# mcu.net
KiCad netlist of a schematic drawn in Altium Designer
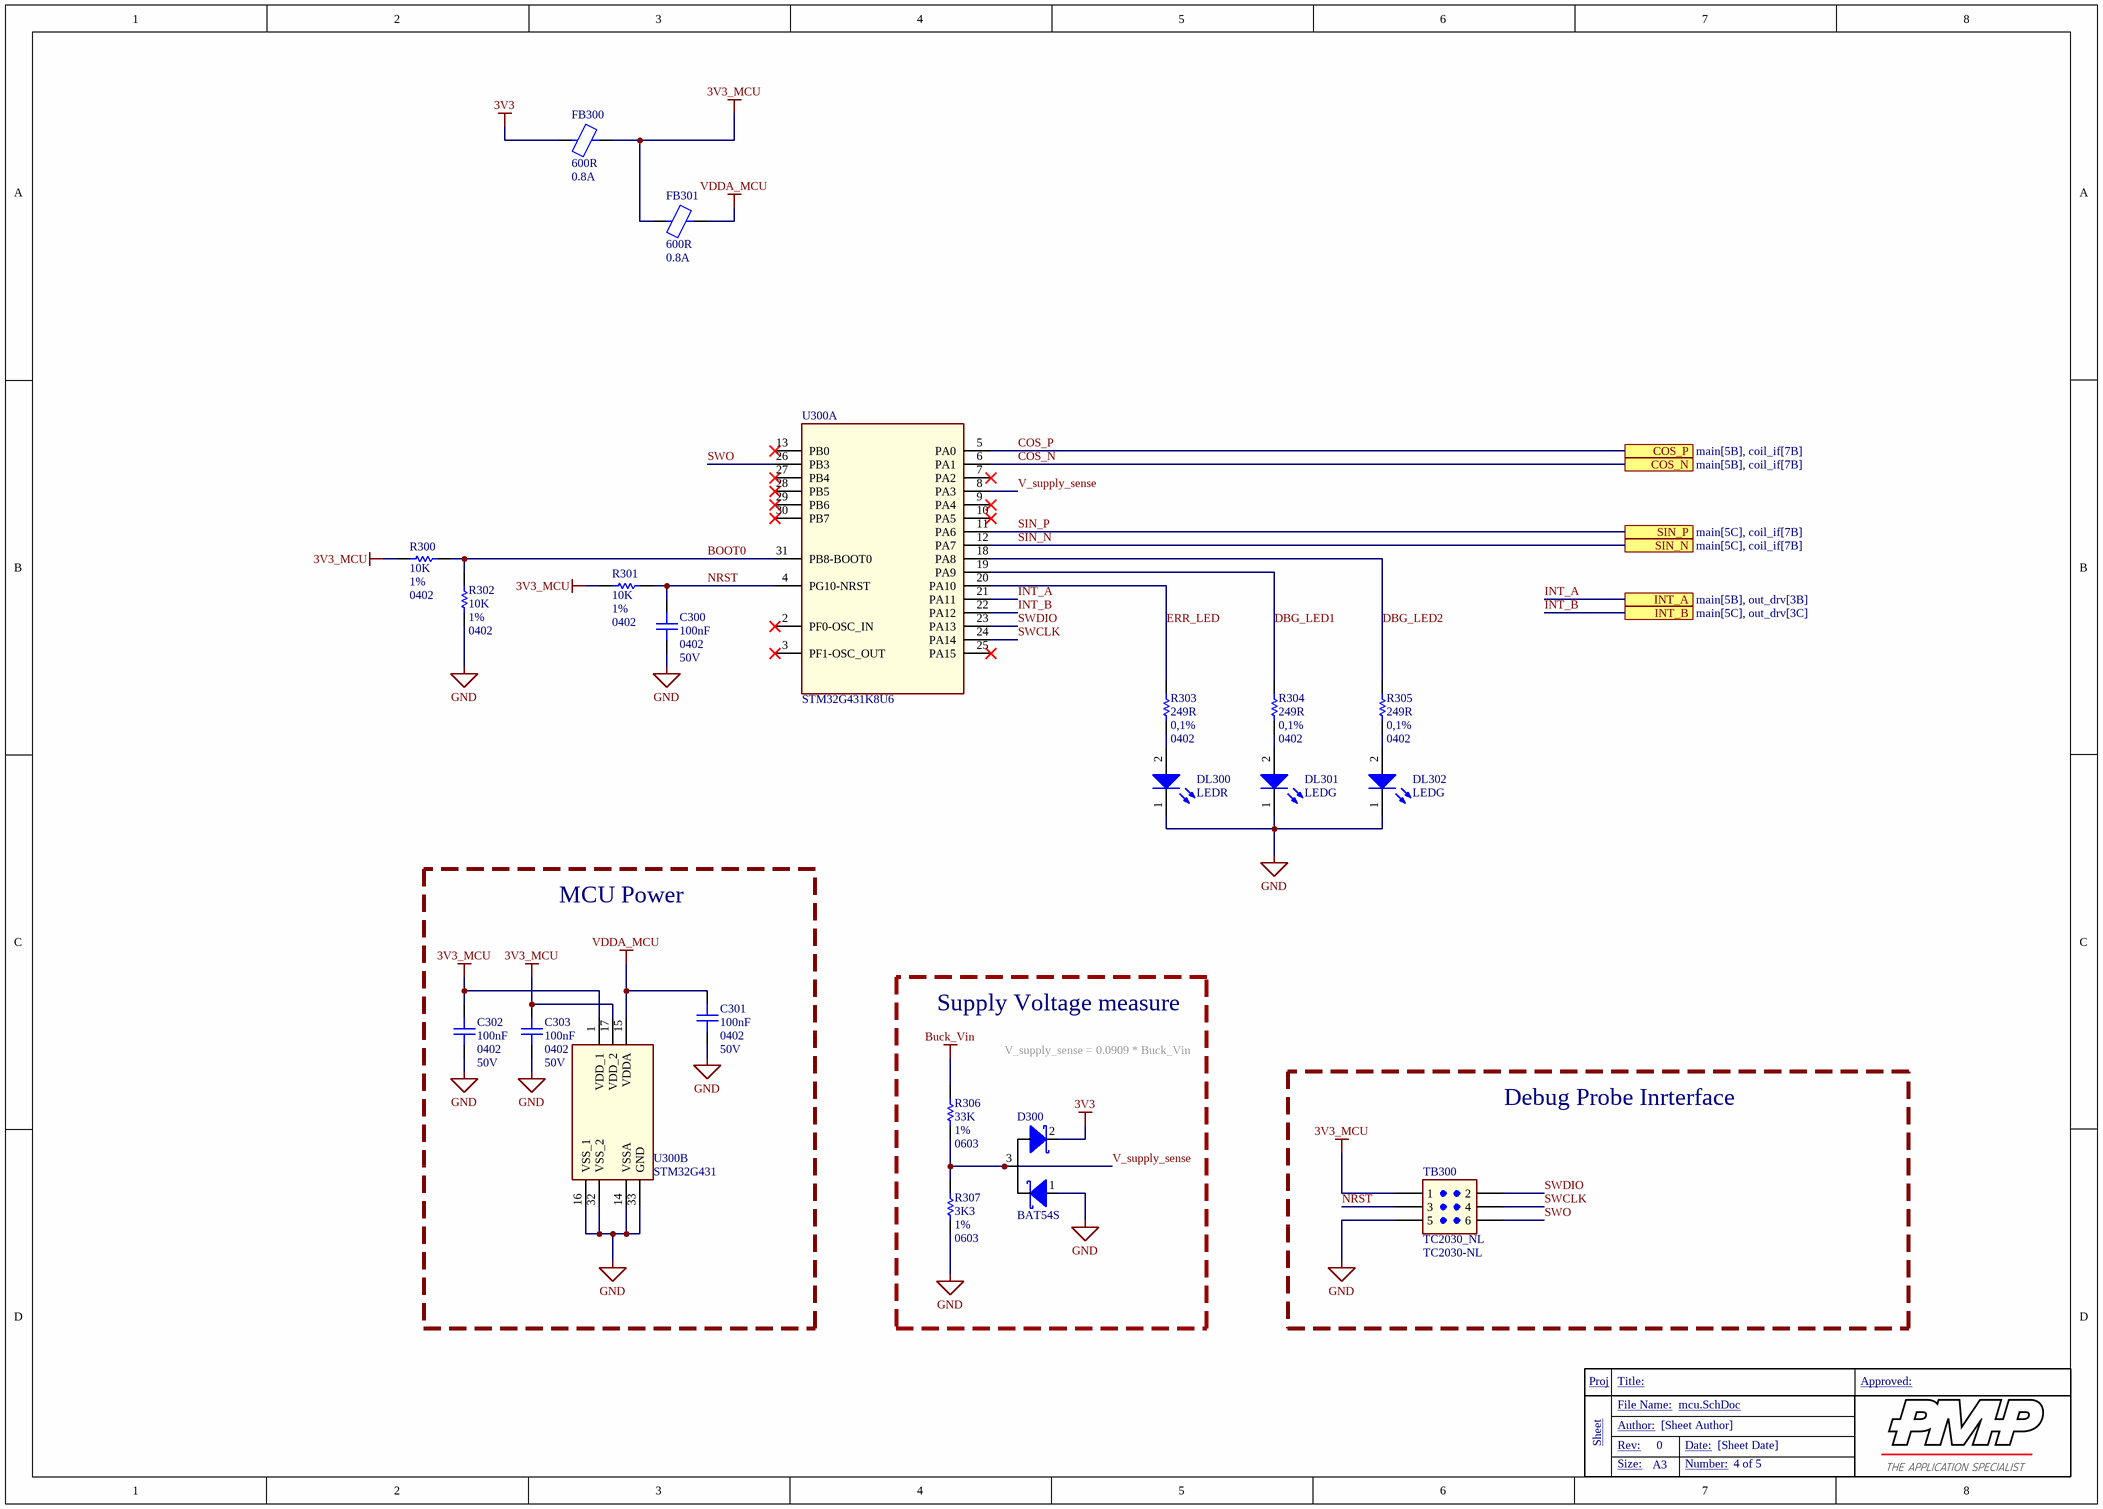
[diagram p0: mcu.SchDoc]

(export (version "E")
  (design (tool "Eeschema 10.0.6"))
  (components
    (comp (ref "C300")
      (value "100nF")
      (footprint "CER0402")
      (description "MLCC Automotive, 100nF, 0402, 50V, 10%, X7r")
      (fields
        (field (name "CASE/PACKAGE") "0402")
        (field (name "OP VOLTAGE") "50V")
        (field (name "TOLERANCE") "10%")
      )
      (libsource (lib "PMP_CapsDB") (part "CapCer_SMD_2"))
    )
    (comp (ref "C301")
      (value "100nF")
      (footprint "CER0402")
      (description "MLCC Automotive, 100nF, 0402, 50V, 10%, X7r")
      (fields
        (field (name "CASE/PACKAGE") "0402")
        (field (name "OP VOLTAGE") "50V")
        (field (name "TOLERANCE") "10%")
      )
      (libsource (lib "PMP_CapsDB") (part "CapCer_SMD_2"))
    )
    (comp (ref "C302")
      (value "100nF")
      (footprint "CER0402")
      (description "MLCC Automotive, 100nF, 0402, 50V, 10%, X7r")
      (fields
        (field (name "CASE/PACKAGE") "0402")
        (field (name "OP VOLTAGE") "50V")
        (field (name "TOLERANCE") "10%")
      )
      (libsource (lib "PMP_CapsDB") (part "CapCer_SMD_2"))
    )
    (comp (ref "C303")
      (value "100nF")
      (footprint "CER0402")
      (description "MLCC Automotive, 100nF, 0402, 50V, 10%, X7r")
      (fields
        (field (name "CASE/PACKAGE") "0402")
        (field (name "OP VOLTAGE") "50V")
        (field (name "TOLERANCE") "10%")
      )
      (libsource (lib "PMP_CapsDB") (part "CapCer_SMD_2"))
    )
    (comp (ref "D300")
      (value "BAT54S")
      (footprint "SOT95P230X110-3N")
      (description "Dual Schottky Diode,  Dual Series, SOT23, 0.2A, 30V")
      (fields (field (name "Comment") "Double Schottky Diode, SOT23-3 series"))
      (libsource (lib "Pmp_DiscretesDB") (part "SchottkyDual_SOT23_ AKC"))
    )
    (comp (ref "DL300")
      (value "LEDR")
      (footprint "LED SMD 0603")
      (description "LED standard - SMD Red 620nm 63mcd 2.2 V, 20mA, 0603 AECQ-102")
      (fields (field (name "Comment") "Single Color SMD LED"))
      (libsource (lib "Pmp_OptoDB") (part "LED_SMD_2_Single"))
    )
    (comp (ref "DL301")
      (value "LEDG")
      (footprint "LED SMD 0603")
      (description "LED standard - SMD Grn 560nm 6.3mcd 2.2 V, 20mA, 0603 AECQ-102")
      (fields (field (name "Comment") "Single Color SMD LED"))
      (libsource (lib "Pmp_OptoDB") (part "LED_SMD_2_Single"))
    )
    (comp (ref "DL302")
      (value "LEDG")
      (footprint "LED SMD 0603")
      (description "LED standard - SMD Grn 560nm 6.3mcd 2.2 V, 20mA, 0603 AECQ-102")
      (fields (field (name "Comment") "Single Color SMD LED"))
      (libsource (lib "Pmp_OptoDB") (part "LED_SMD_2_Single"))
    )
    (comp (ref "FB300")
      (value "~")
      (footprint "FEB0603")
      (description "SMD EMI Suppression Ferrite Bead 600R, 0603, For DC Power")
      (fields (field (name "IMPEDENCE @100MHZ") "600R") (field (name "RATED CURRENT @85°C") "0.8A"))
      (libsource (lib "PMP_FerriteDB") (part "FER_SMD_2_Ferrite_Bead"))
    )
    (comp (ref "FB301")
      (value "~")
      (footprint "FEB0603")
      (description "SMD EMI Suppression Ferrite Bead 600R, 0603, For DC Power")
      (fields (field (name "IMPEDENCE @100MHZ") "600R") (field (name "RATED CURRENT @85°C") "0.8A"))
      (libsource (lib "PMP_FerriteDB") (part "FER_SMD_2_Ferrite_Bead"))
    )
    (comp (ref "R300")
      (value "10K")
      (footprint "Res0402")
      (description "Thick Film SM Chip Resistors, 10K, 0402, ±1%, 1/10W")
      (fields
        (field (name "TOLERANCE") "1%")
        (field (name "CASE/PACKAGE") "0402")
        (field (name "POWER") "63mW")
        (field (name "Comment") "SMD Resistor")
      )
      (libsource (lib "PMP_ResDB") (part "Res_SMD_2"))
    )
    (comp (ref "R301")
      (value "10K")
      (footprint "Res0402")
      (description "Thick Film SM Chip Resistors, 10K, 0402, ±1%, 1/10W")
      (fields
        (field (name "TOLERANCE") "1%")
        (field (name "CASE/PACKAGE") "0402")
        (field (name "POWER") "63mW")
        (field (name "Comment") "SMD Resistor")
      )
      (libsource (lib "PMP_ResDB") (part "Res_SMD_2"))
    )
    (comp (ref "R302")
      (value "10K")
      (footprint "Res0402")
      (description "Thick Film SM Chip Resistors, 10K, 0402, ±1%, 1/10W")
      (fields
        (field (name "TOLERANCE") "1%")
        (field (name "CASE/PACKAGE") "0402")
        (field (name "POWER") "63mW")
        (field (name "Comment") "SMD Resistor")
      )
      (libsource (lib "PMP_ResDB") (part "Res_SMD_2"))
    )
    (comp (ref "R303")
      (value "249R")
      (footprint "Res0402")
      (description "Thick Film SM Chip Resistors, 249R, 0402, ±0.1%, 10ppm 1/16W")
      (fields
        (field (name "TOLERANCE") "0,1%")
        (field (name "CASE/PACKAGE") "0402")
        (field (name "POWER") "63mW")
        (field (name "Comment") "SMD Resistor")
      )
      (libsource (lib "PMP_ResDB") (part "Res_SMD_2"))
    )
    (comp (ref "R304")
      (value "249R")
      (footprint "Res0402")
      (description "Thick Film SM Chip Resistors, 249R, 0402, ±0.1%, 10ppm 1/16W")
      (fields
        (field (name "TOLERANCE") "0,1%")
        (field (name "CASE/PACKAGE") "0402")
        (field (name "POWER") "63mW")
        (field (name "Comment") "SMD Resistor")
      )
      (libsource (lib "PMP_ResDB") (part "Res_SMD_2"))
    )
    (comp (ref "R305")
      (value "249R")
      (footprint "Res0402")
      (description "Thick Film SM Chip Resistors, 249R, 0402, ±0.1%, 10ppm 1/16W")
      (fields
        (field (name "TOLERANCE") "0,1%")
        (field (name "CASE/PACKAGE") "0402")
        (field (name "POWER") "63mW")
        (field (name "Comment") "SMD Resistor")
      )
      (libsource (lib "PMP_ResDB") (part "Res_SMD_2"))
    )
    (comp (ref "R306")
      (value "33K")
      (footprint "Res0603")
      (description "Thick Film SM Chip Resistors, 33K, 0603, ±1%, 1/10W")
      (fields
        (field (name "TOLERANCE") "1%")
        (field (name "CASE/PACKAGE") "0603")
        (field (name "POWER") "100mW")
        (field (name "Comment") "SMD Resistor")
      )
      (libsource (lib "PMP_ResDB") (part "Res_SMD_2"))
    )
    (comp (ref "R307")
      (value "3K3")
      (footprint "Res0603")
      (description "Thick Film SM Chip Resistors, 3K3, 0603, ±1%, 1/10W")
      (fields
        (field (name "TOLERANCE") "1%")
        (field (name "CASE/PACKAGE") "0603")
        (field (name "POWER") "100mW")
        (field (name "Comment") "SMD Resistor")
      )
      (libsource (lib "PMP_ResDB") (part "Res_SMD_2"))
    )
    (comp (ref "TB300")
      (value "TC2030_NL")
      (footprint "TC2030_NL")
      (description "SWDIO pogo pin connector pads")
      (fields (field (name "ALTIUM_VALUE") "TC2030-NL"))
      (libsource (lib "PMP_ConnectorsDB") (part "TC2030_NL"))
    )
    (comp (ref "U300")
      (value "STM32G431")
      (footprint "QFN50P500X500X60-33N")
      (description "MCU  Arm Cortex-M4 MCU 170 MHz -64 KB Flash")
      (fields
        (field (name "MOUSER PART NUMBER") "511-STM32G431K8U6")
        (field (name "MANUFACTURER_PART_NUMBER") "STM32G431K8U6")
      )
      (libsource (lib "PMP_ICsDB") (part "STM32G431K8U6"))
    )
  )
  (nets
    (net (code "1") (name "/BOOT0") (class "Default")
      (node (ref "R300") (pin "1") (pinfunction "1_1") (pintype "passive"))
      (node (ref "R302") (pin "2") (pinfunction "2_2") (pintype "passive"))
      (node (ref "U300") (pin "31") (pinfunction "PB8-BOOT0_31") (pintype "passive"))
    )
    (net (code "2") (name "/COS_N") (class "Default")
      (node (ref "U300") (pin "6") (pinfunction "PA1_6") (pintype "passive"))
    )
    (net (code "3") (name "/COS_P") (class "Default")
      (node (ref "U300") (pin "5") (pinfunction "PA0_5") (pintype "passive"))
    )
    (net (code "4") (name "/DBG_LED1") (class "Default")
      (node (ref "R304") (pin "2") (pinfunction "2_2") (pintype "passive"))
      (node (ref "U300") (pin "19") (pinfunction "PA9_19") (pintype "passive"))
    )
    (net (code "5") (name "/DBG_LED2") (class "Default")
      (node (ref "R305") (pin "2") (pinfunction "2_2") (pintype "passive"))
      (node (ref "U300") (pin "18") (pinfunction "PA8_18") (pintype "passive"))
    )
    (net (code "6") (name "/ERR_LED") (class "Default")
      (node (ref "R303") (pin "2") (pinfunction "2_2") (pintype "passive"))
      (node (ref "U300") (pin "20") (pinfunction "PA10_20") (pintype "passive"))
    )
    (net (code "7") (name "/INT_A") (class "Default")
      (node (ref "U300") (pin "21") (pinfunction "PA11_21") (pintype "passive"))
    )
    (net (code "8") (name "/INT_B") (class "Default")
      (node (ref "U300") (pin "22") (pinfunction "PA12_22") (pintype "passive"))
    )
    (net (code "9") (name "/NRST") (class "Default")
      (node (ref "C300") (pin "1") (pinfunction "1_1") (pintype "passive"))
      (node (ref "R301") (pin "1") (pinfunction "1_1") (pintype "passive"))
      (node (ref "TB300") (pin "3") (pinfunction "3_3") (pintype "passive"))
      (node (ref "U300") (pin "4") (pinfunction "PG10-NRST_4") (pintype "passive"))
    )
    (net (code "10") (name "/SIN_N") (class "Default")
      (node (ref "U300") (pin "12") (pinfunction "PA7_12") (pintype "passive"))
    )
    (net (code "11") (name "/SIN_P") (class "Default")
      (node (ref "U300") (pin "11") (pinfunction "PA6_11") (pintype "passive"))
    )
    (net (code "12") (name "/SWCLK") (class "Default")
      (node (ref "TB300") (pin "4") (pinfunction "4_4") (pintype "passive"))
      (node (ref "U300") (pin "24") (pinfunction "PA14_24") (pintype "passive"))
    )
    (net (code "13") (name "/SWDIO") (class "Default")
      (node (ref "TB300") (pin "2") (pinfunction "2_2") (pintype "passive"))
      (node (ref "U300") (pin "23") (pinfunction "PA13_23") (pintype "passive"))
    )
    (net (code "14") (name "/SWO") (class "Default")
      (node (ref "TB300") (pin "6") (pinfunction "6_6") (pintype "passive"))
      (node (ref "U300") (pin "26") (pinfunction "PB3_26") (pintype "passive"))
    )
    (net (code "15") (name "/V_supply_sense") (class "Default")
      (node (ref "D300") (pin "3") (pinfunction "C_3") (pintype "passive"))
      (node (ref "R306") (pin "1") (pinfunction "1_1") (pintype "passive"))
      (node (ref "R307") (pin "2") (pinfunction "2_2") (pintype "passive"))
      (node (ref "U300") (pin "8") (pinfunction "PA3_8") (pintype "passive"))
    )
    (net (code "16") (name "3V3") (class "Default")
      (node (ref "D300") (pin "2") (pinfunction "K2_2") (pintype "passive"))
      (node (ref "FB300") (pin "1") (pinfunction "1_1") (pintype "passive"))
    )
    (net (code "17") (name "3V3_MCU") (class "Default")
      (node (ref "C302") (pin "1") (pinfunction "1_1") (pintype "passive"))
      (node (ref "C303") (pin "1") (pinfunction "1_1") (pintype "passive"))
      (node (ref "FB300") (pin "2") (pinfunction "2_2") (pintype "passive"))
      (node (ref "FB301") (pin "1") (pinfunction "1_1") (pintype "passive"))
      (node (ref "R300") (pin "2") (pinfunction "2_2") (pintype "passive"))
      (node (ref "R301") (pin "2") (pinfunction "2_2") (pintype "passive"))
      (node (ref "TB300") (pin "1") (pinfunction "1_1") (pintype "passive"))
      (node (ref "U300") (pin "1") (pinfunction "VDD_1_1") (pintype "passive"))
      (node (ref "U300") (pin "17") (pinfunction "VDD_2_17") (pintype "passive"))
    )
    (net (code "18") (name "Buck_Vin") (class "Default")
      (node (ref "R306") (pin "2") (pinfunction "2_2") (pintype "passive"))
    )
    (net (code "19") (name "GND") (class "Default")
      (node (ref "C300") (pin "2") (pinfunction "2_2") (pintype "passive"))
      (node (ref "C301") (pin "2") (pinfunction "2_2") (pintype "passive"))
      (node (ref "C302") (pin "2") (pinfunction "2_2") (pintype "passive"))
      (node (ref "C303") (pin "2") (pinfunction "2_2") (pintype "passive"))
      (node (ref "D300") (pin "1") (pinfunction "A1_1") (pintype "passive"))
      (node (ref "DL300") (pin "1") (pinfunction "K_1") (pintype "passive"))
      (node (ref "DL301") (pin "1") (pinfunction "K_1") (pintype "passive"))
      (node (ref "DL302") (pin "1") (pinfunction "K_1") (pintype "passive"))
      (node (ref "R302") (pin "1") (pinfunction "1_1") (pintype "passive"))
      (node (ref "R307") (pin "1") (pinfunction "1_1") (pintype "passive"))
      (node (ref "TB300") (pin "5") (pinfunction "5_5") (pintype "passive"))
      (node (ref "U300") (pin "14") (pinfunction "VSSA_14") (pintype "passive"))
      (node (ref "U300") (pin "16") (pinfunction "VSS_1_16") (pintype "passive"))
      (node (ref "U300") (pin "32") (pinfunction "VSS_2_32") (pintype "passive"))
      (node (ref "U300") (pin "33") (pinfunction "GND_33") (pintype "passive"))
    )
    (net (code "20") (name "Net-(DL300-A)") (class "Default")
      (node (ref "DL300") (pin "2") (pinfunction "A_2") (pintype "passive"))
      (node (ref "R303") (pin "1") (pinfunction "1_1") (pintype "passive"))
    )
    (net (code "21") (name "Net-(DL301-A)") (class "Default")
      (node (ref "DL301") (pin "2") (pinfunction "A_2") (pintype "passive"))
      (node (ref "R304") (pin "1") (pinfunction "1_1") (pintype "passive"))
    )
    (net (code "22") (name "Net-(DL302-A)") (class "Default")
      (node (ref "DL302") (pin "2") (pinfunction "A_2") (pintype "passive"))
      (node (ref "R305") (pin "1") (pinfunction "1_1") (pintype "passive"))
    )
    (net (code "23") (name "VDDA_MCU") (class "Default")
      (node (ref "C301") (pin "1") (pinfunction "1_1") (pintype "passive"))
      (node (ref "FB301") (pin "2") (pinfunction "2_2") (pintype "passive"))
      (node (ref "U300") (pin "15") (pinfunction "VDDA_15") (pintype "passive"))
    )
    (net (code "24") (name "unconnected-(U300A-PA2-Pad7)") (class "Default")
      (node (ref "U300") (pin "7") (pinfunction "PA2_7") (pintype "passive+no_connect"))
    )
    (net (code "25") (name "unconnected-(U300A-PA4-Pad9)") (class "Default")
      (node (ref "U300") (pin "9") (pinfunction "PA4_9") (pintype "passive+no_connect"))
    )
    (net (code "26") (name "unconnected-(U300A-PA5-Pad10)") (class "Default")
      (node (ref "U300") (pin "10") (pinfunction "PA5_10") (pintype "passive+no_connect"))
    )
    (net (code "27") (name "unconnected-(U300A-PA15-Pad25)") (class "Default")
      (node (ref "U300") (pin "25") (pinfunction "PA15_25") (pintype "passive+no_connect"))
    )
    (net (code "28") (name "unconnected-(U300A-PB0-Pad13)") (class "Default")
      (node (ref "U300") (pin "13") (pinfunction "PB0_13") (pintype "passive+no_connect"))
    )
    (net (code "29") (name "unconnected-(U300A-PB4-Pad27)") (class "Default")
      (node (ref "U300") (pin "27") (pinfunction "PB4_27") (pintype "passive+no_connect"))
    )
    (net (code "30") (name "unconnected-(U300A-PB5-Pad28)") (class "Default")
      (node (ref "U300") (pin "28") (pinfunction "PB5_28") (pintype "passive+no_connect"))
    )
    (net (code "31") (name "unconnected-(U300A-PB6-Pad29)") (class "Default")
      (node (ref "U300") (pin "29") (pinfunction "PB6_29") (pintype "passive+no_connect"))
    )
    (net (code "32") (name "unconnected-(U300A-PB7-Pad30)") (class "Default")
      (node (ref "U300") (pin "30") (pinfunction "PB7_30") (pintype "passive+no_connect"))
    )
    (net (code "33") (name "unconnected-(U300A-PF0-OSC_IN-Pad2)") (class "Default")
      (node (ref "U300") (pin "2") (pinfunction "PF0-OSC_IN_2") (pintype "passive+no_connect"))
    )
    (net (code "34") (name "unconnected-(U300A-PF1-OSC_OUT-Pad3)") (class "Default")
      (node (ref "U300") (pin "3") (pinfunction "PF1-OSC_OUT_3") (pintype "passive+no_connect"))
    )
  )
)
